# stspin32f0_rev_0_9.net
KiCad netlist of a schematic drawn in EAGLE
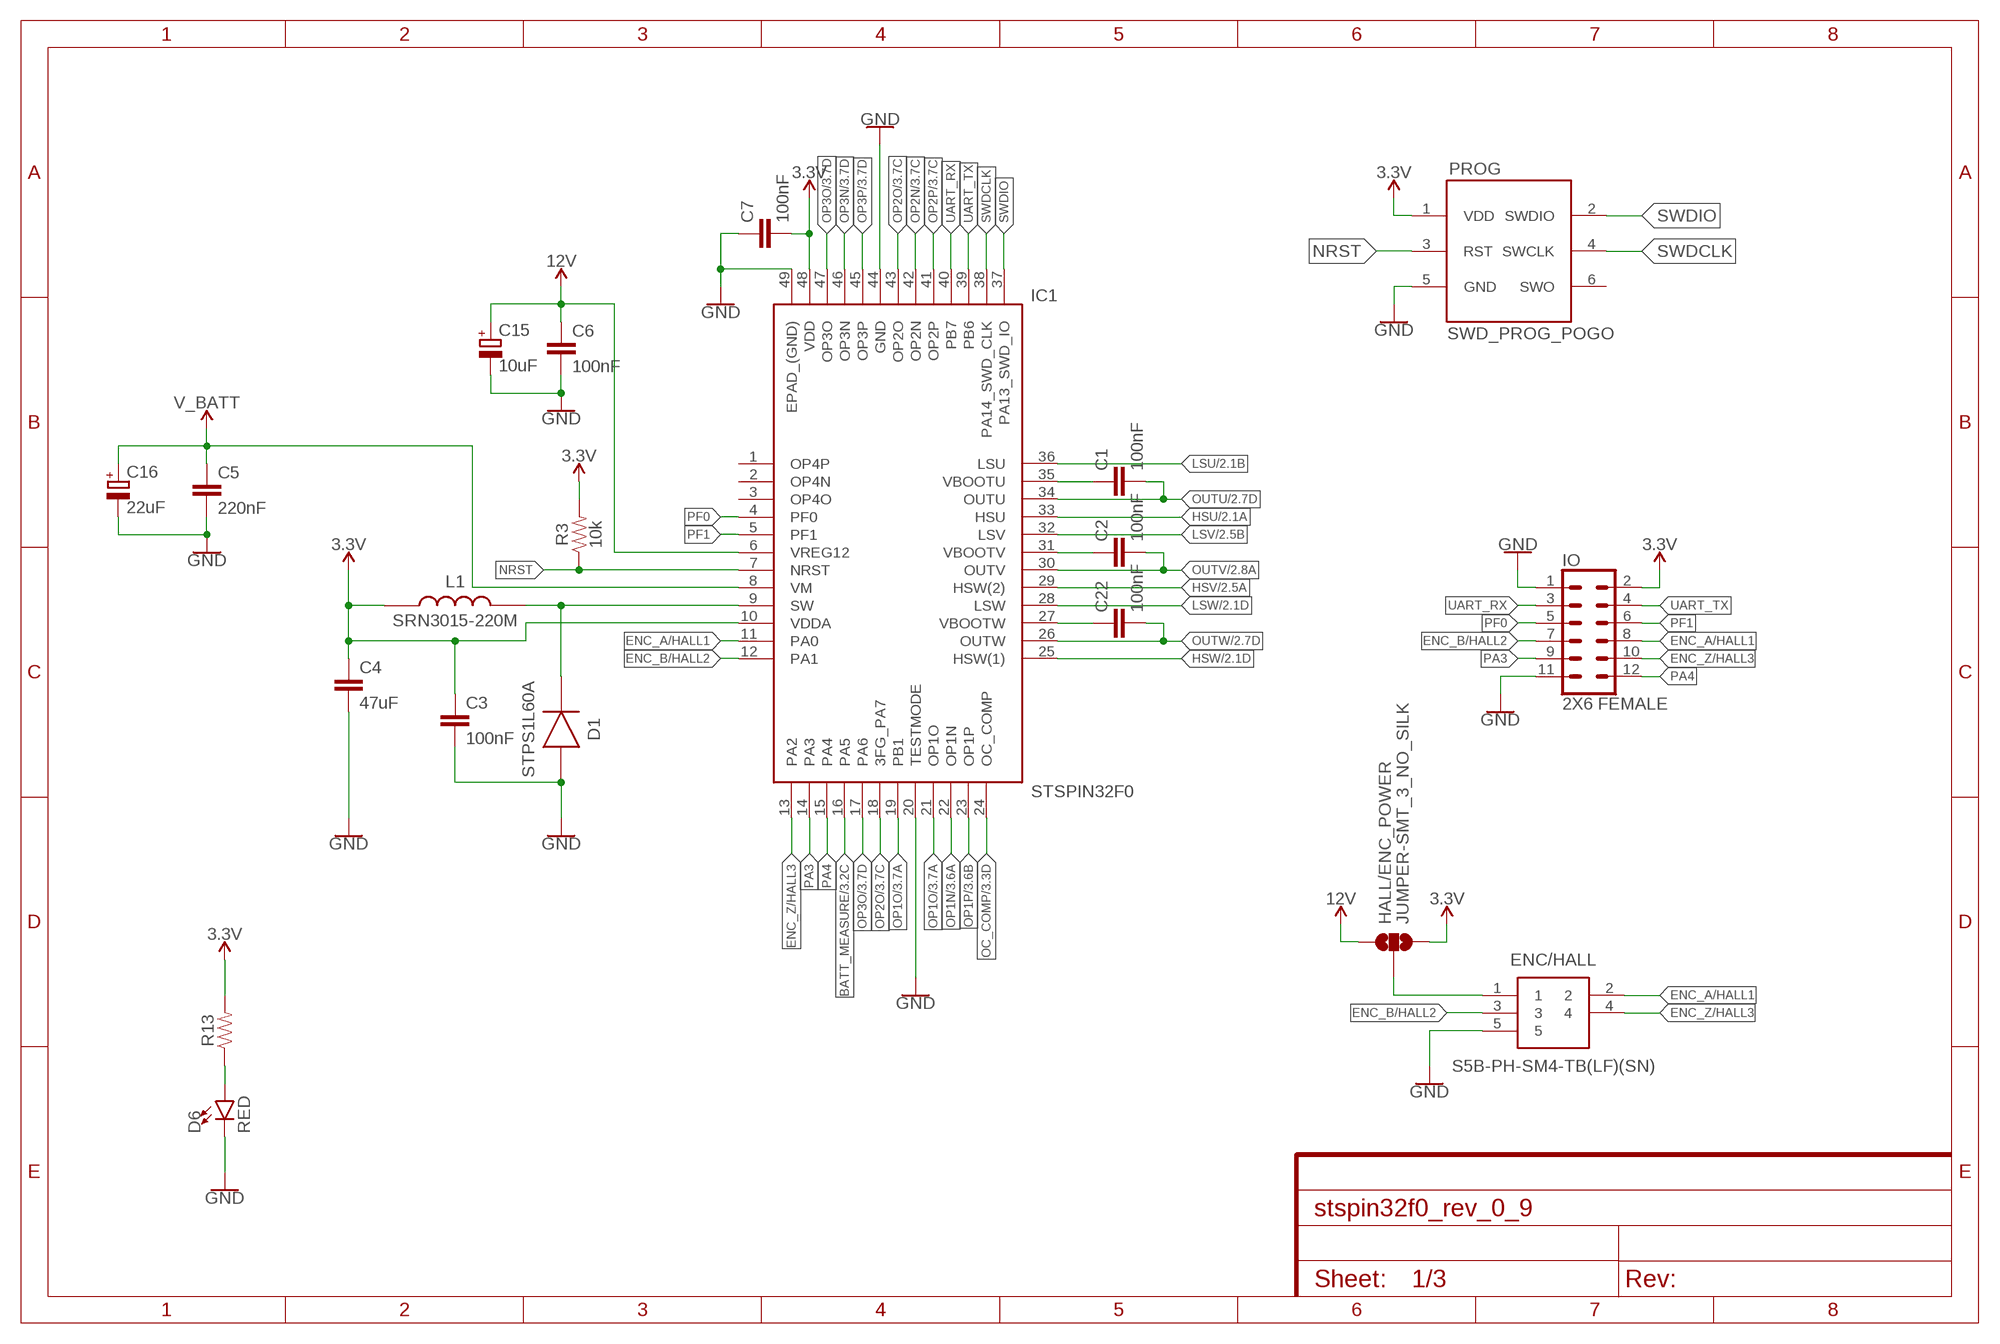
[diagram p0: schematic, sheet 1]
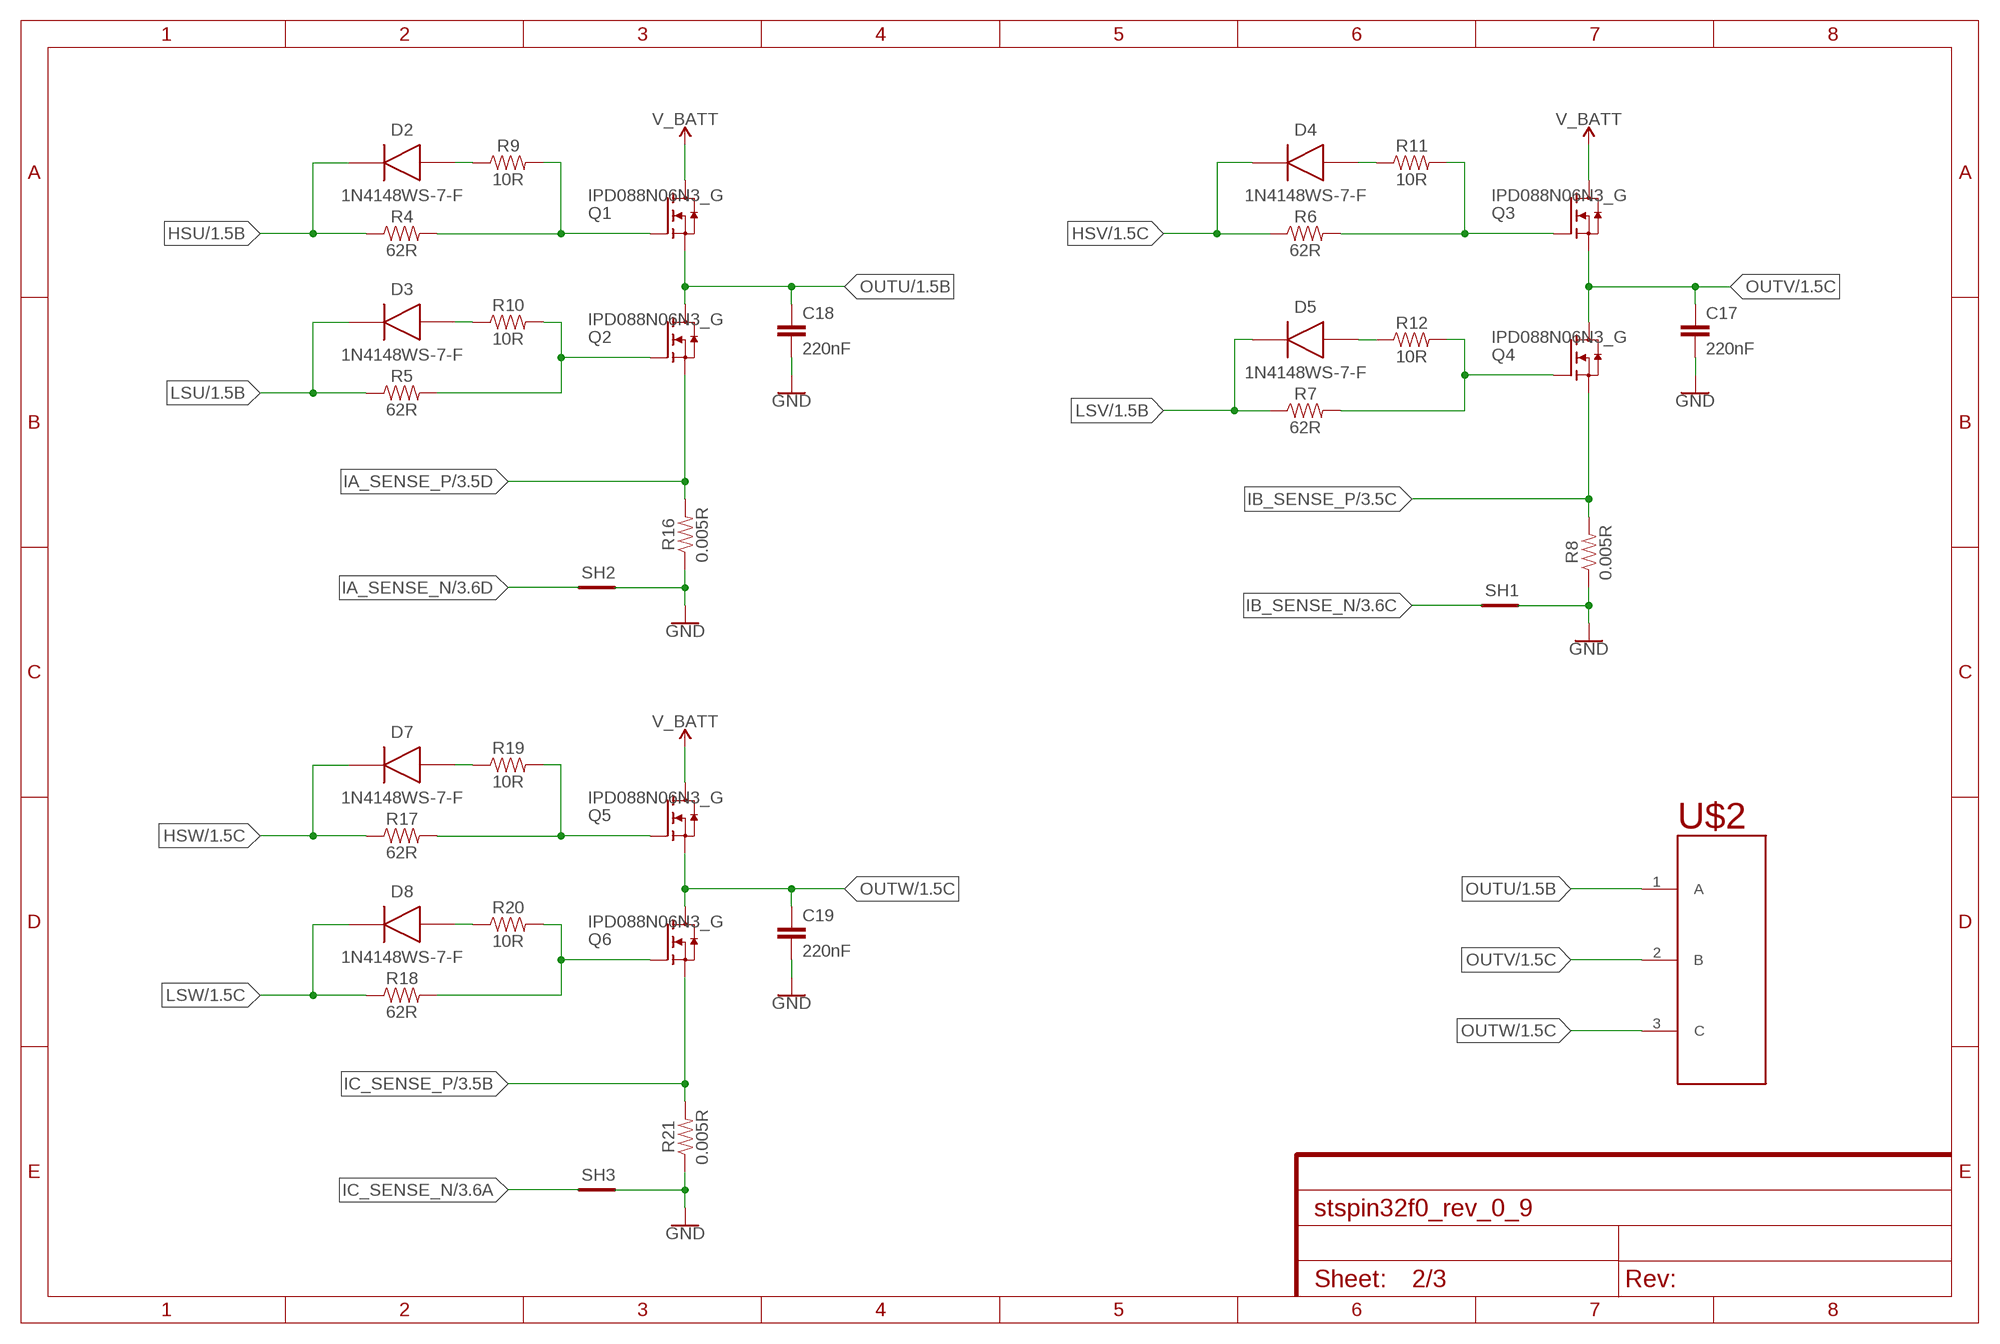
[diagram p1: schematic, sheet 2]
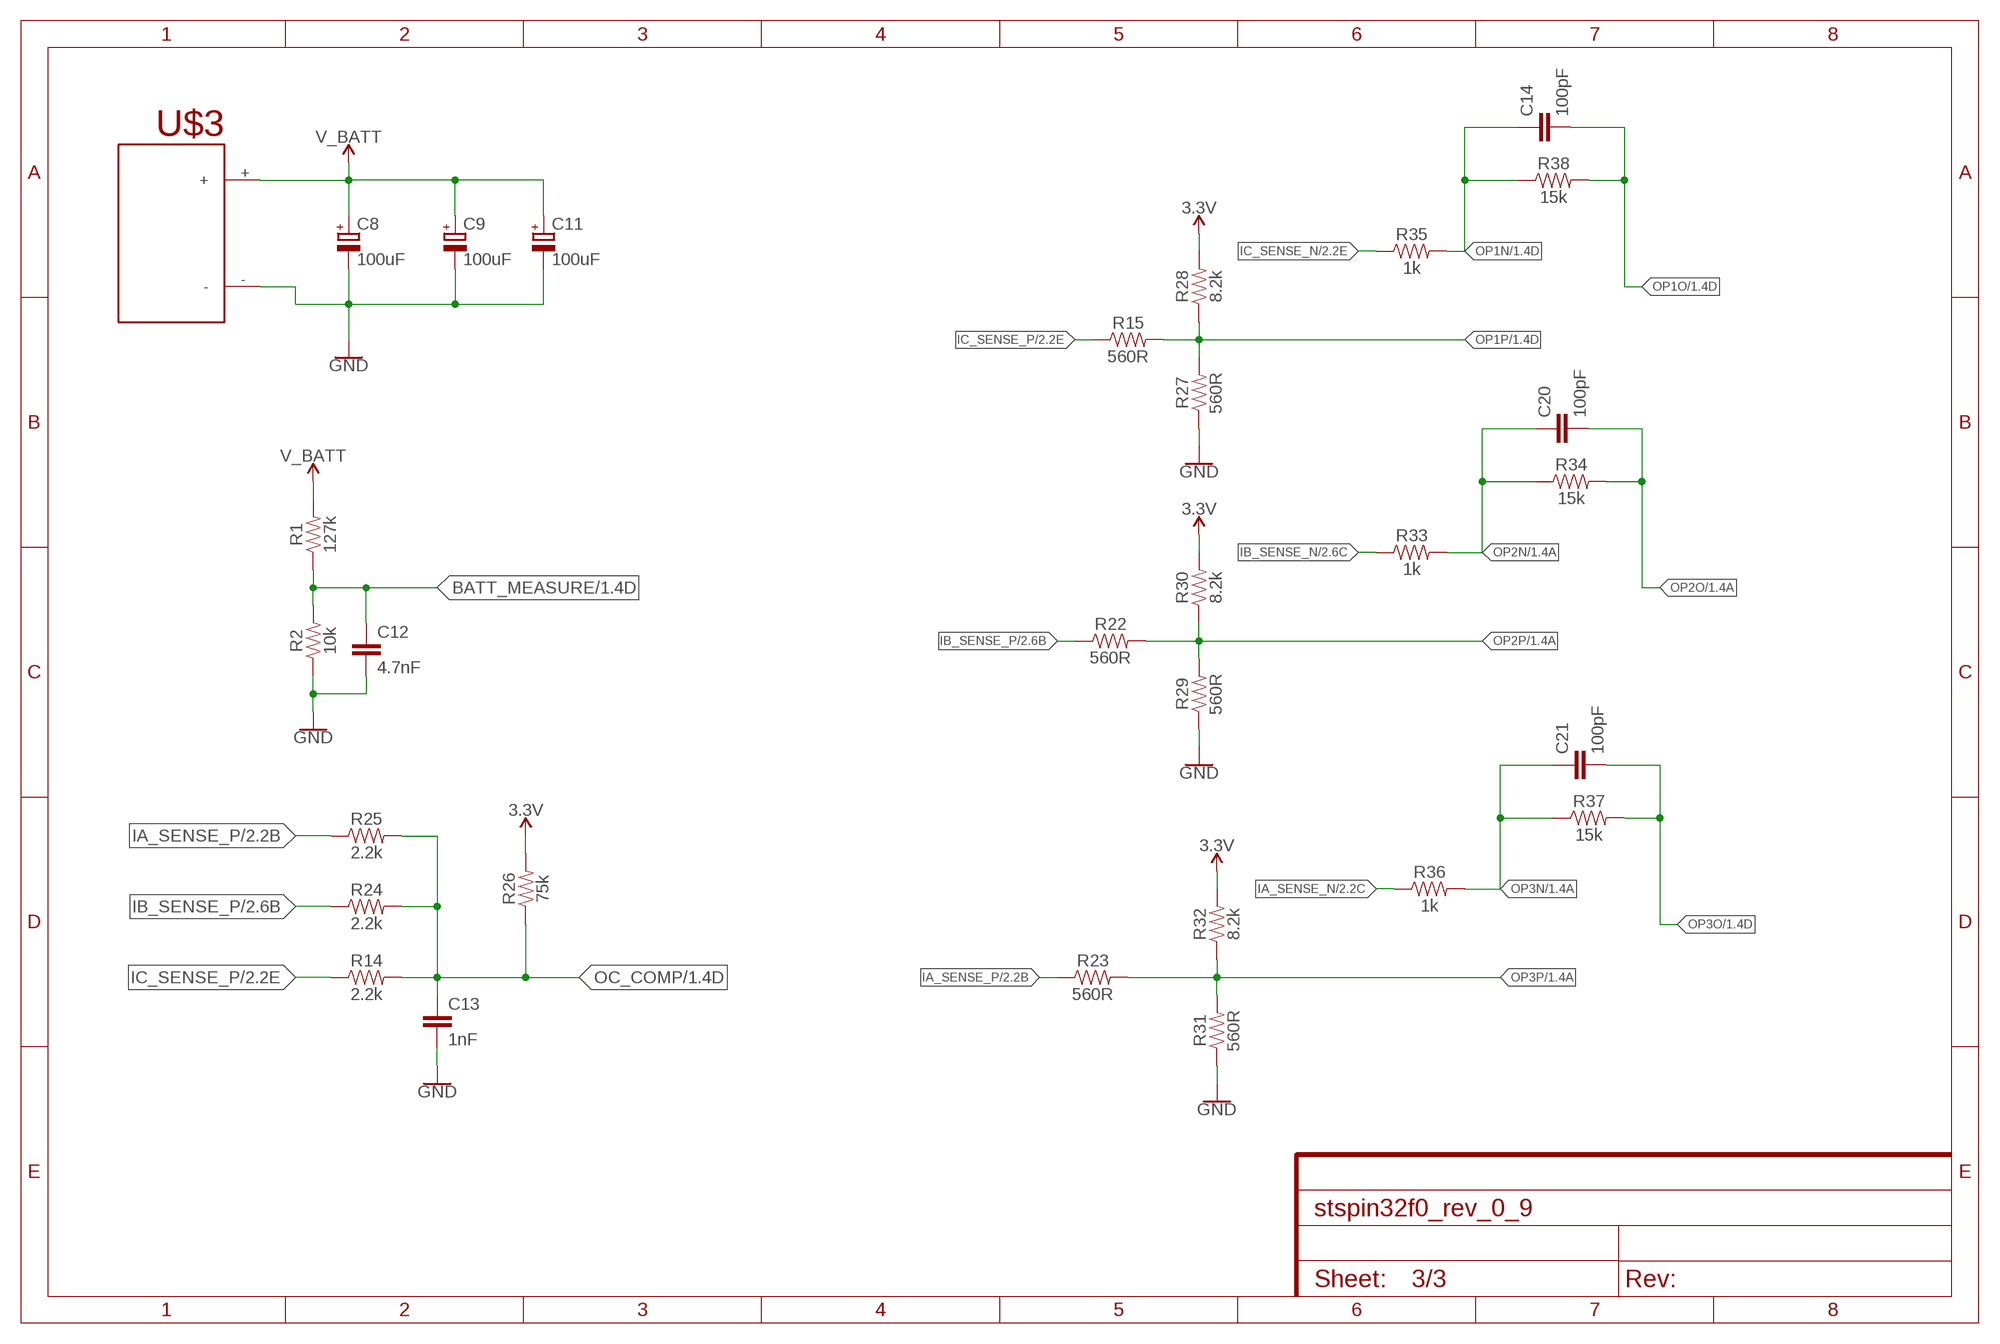
[diagram p2: schematic, sheet 3]

(export (version "E")
  (design (tool "Eeschema 10.0.6"))
  (components
    (comp (ref "C1")
      (value "100nF")
      (footprint "eagle-import:0603")
      (libsource (lib "eagle-import") (part "CAP-50V-10%-0603"))
    )
    (comp (ref "C2")
      (value "100nF")
      (footprint "eagle-import:0603")
      (libsource (lib "eagle-import") (part "CAP-50V-10%-0603"))
    )
    (comp (ref "C3")
      (value "100nF")
      (footprint "eagle-import:0603")
      (libsource (lib "eagle-import") (part "CAP-10V-20%-0603"))
    )
    (comp (ref "C4")
      (value "47uF")
      (footprint "eagle-import:0805")
      (libsource (lib "eagle-import") (part "CAP-10V-20%-0805"))
    )
    (comp (ref "C5")
      (value "220nF")
      (footprint "eagle-import:0805")
      (libsource (lib "eagle-import") (part "CAP-50V-10%-0805"))
    )
    (comp (ref "C6")
      (value "100nF")
      (footprint "eagle-import:0603")
      (libsource (lib "eagle-import") (part "CAP-25V-20%-0603"))
    )
    (comp (ref "C7")
      (value "100nF")
      (footprint "eagle-import:0603")
      (libsource (lib "eagle-import") (part "CAP-10V-20%-0603"))
    )
    (comp (ref "C15")
      (value "10uF")
      (footprint "eagle-import:UD-5X5,8_NICHICON")
      (libsource (lib "eagle-import") (part "CPOL-EUUD-5X5,8"))
    )
    (comp (ref "C16")
      (value "22uF")
      (footprint "eagle-import:UD-6,3X5,8_NICHICON")
      (libsource (lib "eagle-import") (part "CPOL-EUUD-6,3X8,8"))
    )
    (comp (ref "C22")
      (value "100nF")
      (footprint "eagle-import:0603")
      (libsource (lib "eagle-import") (part "CAP-50V-10%-0603"))
    )
    (comp (ref "D1")
      (value "STPS1L60A")
      (footprint "eagle-import:DIOM5126X265N")
      (fields (field (name "RS_PART_NUMBER") "250549"))
      (libsource (lib "eagle-import") (part "STPS1L60A"))
    )
    (comp (ref "D6")
      (value "RED")
      (footprint "eagle-import:LED-0603")
      (libsource (lib "eagle-import") (part "LED-RED0603"))
    )
    (comp (ref "ENC/HALL")
      (value "S5B-PH-SM4-TB(LF)(SN)")
      (footprint "eagle-import:S5B-PH-SM4-TB_1")
      (libsource (lib "eagle-import") (part "S5B-PH-SM4-TB(LF)(SN)"))
    )
    (comp (ref "HALL/ENC_POWER")
      (value "JUMPER-SMT_3_NO_SILK")
      (footprint "eagle-import:SMT-JUMPER_3_NO_SILK")
      (libsource (lib "eagle-import") (part "JUMPER-SMT_3_NO_SILK"))
    )
    (comp (ref "IC1")
      (value "STSPIN32F0")
      (footprint "eagle-import:QFN50P700X700X100-49N")
      (libsource (lib "eagle-import") (part "STSPIN32F0"))
    )
    (comp (ref "IO")
      (value "2X6 FEMALE")
      (footprint "eagle-import:2X6")
      (libsource (lib "eagle-import") (part "CONN_06X2PTH_FEMALE"))
    )
    (comp (ref "L1")
      (value "SRN3015-220M")
      (footprint "eagle-import:SRN3015")
      (fields (field (name "RS_PART_NUMBER") "7435087"))
      (libsource (lib "eagle-import") (part "SRN3015-220M"))
    )
    (comp (ref "PROG")
      (value "SWD_PROG_POGO")
      (footprint "eagle-import:1X06_1.27MM")
      (libsource (lib "eagle-import") (part "SWD_PROG_POGO"))
    )
    (comp (ref "R3")
      (value "10k")
      (footprint "eagle-import:0603")
      (libsource (lib "eagle-import") (part "RES-1/10W-5%-0603"))
    )
    (comp (ref "R13")
      (value "RES-1/10W-5%-0603")
      (footprint "eagle-import:0603")
      (libsource (lib "eagle-import") (part "RES-1/10W-5%-0603"))
    )
    (comp (ref "C17")
      (value "220nF")
      (footprint "eagle-import:0805")
      (libsource (lib "eagle-import") (part "CAP-50V-10%-0805"))
    )
    (comp (ref "C18")
      (value "220nF")
      (footprint "eagle-import:0805")
      (libsource (lib "eagle-import") (part "CAP-50V-10%-0805"))
    )
    (comp (ref "C19")
      (value "220nF")
      (footprint "eagle-import:0805")
      (libsource (lib "eagle-import") (part "CAP-50V-10%-0805"))
    )
    (comp (ref "D2")
      (value "1N4148WS-7-F")
      (footprint "eagle-import:SOD2513X120N")
      (fields (field (name "RS_PART_NUMBER") "9228070"))
      (libsource (lib "eagle-import") (part "1N4148WS-7-F"))
    )
    (comp (ref "D3")
      (value "1N4148WS-7-F")
      (footprint "eagle-import:SOD2513X120N")
      (fields (field (name "RS_PART_NUMBER") "9228070"))
      (libsource (lib "eagle-import") (part "1N4148WS-7-F"))
    )
    (comp (ref "D4")
      (value "1N4148WS-7-F")
      (footprint "eagle-import:SOD2513X120N")
      (fields (field (name "RS_PART_NUMBER") "9228070"))
      (libsource (lib "eagle-import") (part "1N4148WS-7-F"))
    )
    (comp (ref "D5")
      (value "1N4148WS-7-F")
      (footprint "eagle-import:SOD2513X120N")
      (fields (field (name "RS_PART_NUMBER") "9228070"))
      (libsource (lib "eagle-import") (part "1N4148WS-7-F"))
    )
    (comp (ref "D7")
      (value "1N4148WS-7-F")
      (footprint "eagle-import:SOD2513X120N")
      (fields (field (name "RS_PART_NUMBER") "9228070"))
      (libsource (lib "eagle-import") (part "1N4148WS-7-F"))
    )
    (comp (ref "D8")
      (value "1N4148WS-7-F")
      (footprint "eagle-import:SOD2513X120N")
      (fields (field (name "RS_PART_NUMBER") "9228070"))
      (libsource (lib "eagle-import") (part "1N4148WS-7-F"))
    )
    (comp (ref "Q1")
      (value "IPD088N06N3_G")
      (footprint "eagle-import:DPAK(TO-252-3)")
      (fields (field (name "MANUFACTURER_PART_NUMBER") "IPD088N06N3 G"))
      (libsource (lib "eagle-import") (part "IPD088N06N3_G"))
    )
    (comp (ref "Q2")
      (value "IPD088N06N3_G")
      (footprint "eagle-import:DPAK(TO-252-3)")
      (fields (field (name "MANUFACTURER_PART_NUMBER") "IPD088N06N3 G"))
      (libsource (lib "eagle-import") (part "IPD088N06N3_G"))
    )
    (comp (ref "Q3")
      (value "IPD088N06N3_G")
      (footprint "eagle-import:DPAK(TO-252-3)")
      (fields (field (name "MANUFACTURER_PART_NUMBER") "IPD088N06N3 G"))
      (libsource (lib "eagle-import") (part "IPD088N06N3_G"))
    )
    (comp (ref "Q4")
      (value "IPD088N06N3_G")
      (footprint "eagle-import:DPAK(TO-252-3)")
      (fields (field (name "MANUFACTURER_PART_NUMBER") "IPD088N06N3 G"))
      (libsource (lib "eagle-import") (part "IPD088N06N3_G"))
    )
    (comp (ref "Q5")
      (value "IPD088N06N3_G")
      (footprint "eagle-import:DPAK(TO-252-3)")
      (fields (field (name "MANUFACTURER_PART_NUMBER") "IPD088N06N3 G"))
      (libsource (lib "eagle-import") (part "IPD088N06N3_G"))
    )
    (comp (ref "Q6")
      (value "IPD088N06N3_G")
      (footprint "eagle-import:DPAK(TO-252-3)")
      (fields (field (name "MANUFACTURER_PART_NUMBER") "IPD088N06N3 G"))
      (libsource (lib "eagle-import") (part "IPD088N06N3_G"))
    )
    (comp (ref "R4")
      (value "62R")
      (footprint "eagle-import:0603")
      (libsource (lib "eagle-import") (part "RES-1/10W-5%-0603"))
    )
    (comp (ref "R5")
      (value "62R")
      (footprint "eagle-import:0603")
      (libsource (lib "eagle-import") (part "RES-1/10W-5%-0603"))
    )
    (comp (ref "R6")
      (value "62R")
      (footprint "eagle-import:0603")
      (libsource (lib "eagle-import") (part "RES-1/10W-5%-0603"))
    )
    (comp (ref "R7")
      (value "62R")
      (footprint "eagle-import:0603")
      (libsource (lib "eagle-import") (part "RES-1/10W-5%-0603"))
    )
    (comp (ref "R8")
      (value "0.005R")
      (footprint "eagle-import:R2512")
      (libsource (lib "eagle-import") (part "RES-3W-1%-2512"))
    )
    (comp (ref "R9")
      (value "10R")
      (footprint "eagle-import:0603")
      (libsource (lib "eagle-import") (part "RES-1/10W-5%-0603"))
    )
    (comp (ref "R10")
      (value "10R")
      (footprint "eagle-import:0603")
      (libsource (lib "eagle-import") (part "RES-1/10W-5%-0603"))
    )
    (comp (ref "R11")
      (value "10R")
      (footprint "eagle-import:0603")
      (libsource (lib "eagle-import") (part "RES-1/10W-5%-0603"))
    )
    (comp (ref "R12")
      (value "10R")
      (footprint "eagle-import:0603")
      (libsource (lib "eagle-import") (part "RES-1/10W-5%-0603"))
    )
    (comp (ref "R16")
      (value "0.005R")
      (footprint "eagle-import:R2512")
      (libsource (lib "eagle-import") (part "RES-3W-1%-2512"))
    )
    (comp (ref "R17")
      (value "62R")
      (footprint "eagle-import:0603")
      (libsource (lib "eagle-import") (part "RES-1/10W-5%-0603"))
    )
    (comp (ref "R18")
      (value "62R")
      (footprint "eagle-import:0603")
      (libsource (lib "eagle-import") (part "RES-1/10W-5%-0603"))
    )
    (comp (ref "R19")
      (value "10R")
      (footprint "eagle-import:0603")
      (libsource (lib "eagle-import") (part "RES-1/10W-5%-0603"))
    )
    (comp (ref "R20")
      (value "10R")
      (footprint "eagle-import:0603")
      (libsource (lib "eagle-import") (part "RES-1/10W-5%-0603"))
    )
    (comp (ref "R21")
      (value "0.005R")
      (footprint "eagle-import:R2512")
      (libsource (lib "eagle-import") (part "RES-3W-1%-2512"))
    )
    (comp (ref "SH1")
      (value "SHORTT5")
      (footprint "eagle-import:SHORT_TOP-50")
      (libsource (lib "eagle-import") (part "SHORTT5"))
    )
    (comp (ref "SH2")
      (value "SHORTT5")
      (footprint "eagle-import:SHORT_TOP-50")
      (libsource (lib "eagle-import") (part "SHORTT5"))
    )
    (comp (ref "SH3")
      (value "SHORTT5")
      (footprint "eagle-import:SHORT_TOP-50")
      (libsource (lib "eagle-import") (part "SHORTT5"))
    )
    (comp (ref "U$2")
      (value "MR30")
      (footprint "eagle-import:MR30PW")
      (libsource (lib "eagle-import") (part "MR30"))
    )
    (comp (ref "C8")
      (value "100uF")
      (footprint "eagle-import:UD-6,3X7,7_NICHICON")
      (libsource (lib "eagle-import") (part "CPOL-EUUD-6,3X7,7"))
    )
    (comp (ref "C9")
      (value "100uF")
      (footprint "eagle-import:UD-6,3X7,7_NICHICON")
      (libsource (lib "eagle-import") (part "CPOL-EUUD-6,3X7,7"))
    )
    (comp (ref "C11")
      (value "100uF")
      (footprint "eagle-import:UD-6,3X7,7_NICHICON")
      (libsource (lib "eagle-import") (part "CPOL-EUUD-6,3X7,7"))
    )
    (comp (ref "C12")
      (value "4.7nF")
      (footprint "eagle-import:0603")
      (libsource (lib "eagle-import") (part "CAP-25V-20%-0603"))
    )
    (comp (ref "C13")
      (value "1nF")
      (footprint "eagle-import:0603")
      (libsource (lib "eagle-import") (part "CAP-25V-20%-0603"))
    )
    (comp (ref "C14")
      (value "100pF")
      (footprint "eagle-import:0603")
      (libsource (lib "eagle-import") (part "CAP-25V-20%-0603"))
    )
    (comp (ref "C20")
      (value "100pF")
      (footprint "eagle-import:0603")
      (libsource (lib "eagle-import") (part "CAP-25V-20%-0603"))
    )
    (comp (ref "C21")
      (value "100pF")
      (footprint "eagle-import:0603")
      (libsource (lib "eagle-import") (part "CAP-25V-20%-0603"))
    )
    (comp (ref "R1")
      (value "127k")
      (footprint "eagle-import:0603")
      (libsource (lib "eagle-import") (part "RES-1/10W-1%-0603"))
    )
    (comp (ref "R2")
      (value "10k")
      (footprint "eagle-import:0603")
      (libsource (lib "eagle-import") (part "RES-1/10W-1%-0603"))
    )
    (comp (ref "R14")
      (value "2.2k")
      (footprint "eagle-import:0603")
      (libsource (lib "eagle-import") (part "RES-1/10W-5%-0603"))
    )
    (comp (ref "R15")
      (value "560R")
      (footprint "eagle-import:0603")
      (libsource (lib "eagle-import") (part "RES-1/10W-5%-0603"))
    )
    (comp (ref "R22")
      (value "560R")
      (footprint "eagle-import:0603")
      (libsource (lib "eagle-import") (part "RES-1/10W-5%-0603"))
    )
    (comp (ref "R23")
      (value "560R")
      (footprint "eagle-import:0603")
      (libsource (lib "eagle-import") (part "RES-1/10W-5%-0603"))
    )
    (comp (ref "R24")
      (value "2.2k")
      (footprint "eagle-import:0603")
      (libsource (lib "eagle-import") (part "RES-1/10W-5%-0603"))
    )
    (comp (ref "R25")
      (value "2.2k")
      (footprint "eagle-import:0603")
      (libsource (lib "eagle-import") (part "RES-1/10W-5%-0603"))
    )
    (comp (ref "R26")
      (value "75k")
      (footprint "eagle-import:0603")
      (libsource (lib "eagle-import") (part "RES-1/10W-1%-0603"))
    )
    (comp (ref "R27")
      (value "560R")
      (footprint "eagle-import:0603")
      (libsource (lib "eagle-import") (part "RES-1/10W-5%-0603"))
    )
    (comp (ref "R28")
      (value "8.2k")
      (footprint "eagle-import:0603")
      (libsource (lib "eagle-import") (part "RES-1/10W-5%-0603"))
    )
    (comp (ref "R29")
      (value "560R")
      (footprint "eagle-import:0603")
      (libsource (lib "eagle-import") (part "RES-1/10W-5%-0603"))
    )
    (comp (ref "R30")
      (value "8.2k")
      (footprint "eagle-import:0603")
      (libsource (lib "eagle-import") (part "RES-1/10W-5%-0603"))
    )
    (comp (ref "R31")
      (value "560R")
      (footprint "eagle-import:0603")
      (libsource (lib "eagle-import") (part "RES-1/10W-5%-0603"))
    )
    (comp (ref "R32")
      (value "8.2k")
      (footprint "eagle-import:0603")
      (libsource (lib "eagle-import") (part "RES-1/10W-5%-0603"))
    )
    (comp (ref "R33")
      (value "1k")
      (footprint "eagle-import:0603")
      (libsource (lib "eagle-import") (part "RES-1/10W-5%-0603"))
    )
    (comp (ref "R34")
      (value "15k")
      (footprint "eagle-import:0603")
      (libsource (lib "eagle-import") (part "RES-1/10W-5%-0603"))
    )
    (comp (ref "R35")
      (value "1k")
      (footprint "eagle-import:0603")
      (libsource (lib "eagle-import") (part "RES-1/10W-5%-0603"))
    )
    (comp (ref "R36")
      (value "1k")
      (footprint "eagle-import:0603")
      (libsource (lib "eagle-import") (part "RES-1/10W-5%-0603"))
    )
    (comp (ref "R37")
      (value "15k")
      (footprint "eagle-import:0603")
      (libsource (lib "eagle-import") (part "RES-1/10W-5%-0603"))
    )
    (comp (ref "R38")
      (value "15k")
      (footprint "eagle-import:0603")
      (libsource (lib "eagle-import") (part "RES-1/10W-5%-0603"))
    )
    (comp (ref "U$3")
      (value "XT30")
      (footprint "eagle-import:XT30PW")
      (libsource (lib "eagle-import") (part "XT30"))
    )
  )
  (nets
    (net (code "1") (name "3.3V") (class "Default")
      (node (ref "C3") (pin "1") (pinfunction "1_1") (pintype "passive"))
      (node (ref "C4") (pin "1") (pinfunction "1_1") (pintype "passive"))
      (node (ref "C7") (pin "2") (pinfunction "2_2") (pintype "passive"))
      (node (ref "HALL/ENC_POWER") (pin "3") (pinfunction "3_3") (pintype "passive"))
      (node (ref "IC1") (pin "10") (pinfunction "VDDA_10") (pintype "input"))
      (node (ref "IC1") (pin "48") (pinfunction "VDD_48") (pintype "input"))
      (node (ref "IO") (pin "2") (pinfunction "2_2") (pintype "passive"))
      (node (ref "L1") (pin "1") (pinfunction "1_1") (pintype "bidirectional"))
      (node (ref "PROG") (pin "1") (pinfunction "VDD_1") (pintype "bidirectional"))
      (node (ref "R13") (pin "2") (pinfunction "2_2") (pintype "passive"))
      (node (ref "R26") (pin "2") (pinfunction "2_2") (pintype "passive"))
      (node (ref "R28") (pin "2") (pinfunction "2_2") (pintype "passive"))
      (node (ref "R3") (pin "2") (pinfunction "2_2") (pintype "passive"))
      (node (ref "R30") (pin "2") (pinfunction "2_2") (pintype "passive"))
      (node (ref "R32") (pin "2") (pinfunction "2_2") (pintype "passive"))
    )
    (net (code "2") (name "12V") (class "Default")
      (node (ref "C15") (pin "+") (pinfunction "+_+") (pintype "passive"))
      (node (ref "C6") (pin "1") (pinfunction "1_1") (pintype "passive"))
      (node (ref "HALL/ENC_POWER") (pin "1") (pinfunction "1_1") (pintype "passive"))
      (node (ref "IC1") (pin "6") (pinfunction "VREG12_6") (pintype "input"))
    )
    (net (code "3") (name "BATT_MEASURE") (class "Default")
      (node (ref "C12") (pin "1") (pinfunction "1_1") (pintype "passive"))
      (node (ref "IC1") (pin "16") (pinfunction "PA5_16") (pintype "input"))
      (node (ref "R1") (pin "1") (pinfunction "1_1") (pintype "passive"))
      (node (ref "R2") (pin "2") (pinfunction "2_2") (pintype "passive"))
    )
    (net (code "4") (name "ENC_A{slash}HALL1") (class "Default")
      (node (ref "ENC/HALL") (pin "2") (pinfunction "2_2") (pintype "input"))
      (node (ref "IC1") (pin "11") (pinfunction "PA0_11") (pintype "input"))
      (node (ref "IO") (pin "8") (pinfunction "8_8") (pintype "passive"))
    )
    (net (code "5") (name "ENC_B{slash}HALL2") (class "Default")
      (node (ref "ENC/HALL") (pin "3") (pinfunction "3_3") (pintype "input"))
      (node (ref "IC1") (pin "12") (pinfunction "PA1_12") (pintype "input"))
      (node (ref "IO") (pin "7") (pinfunction "7_7") (pintype "passive"))
    )
    (net (code "6") (name "ENC_Z{slash}HALL3") (class "Default")
      (node (ref "ENC/HALL") (pin "4") (pinfunction "4_4") (pintype "input"))
      (node (ref "IC1") (pin "13") (pinfunction "PA2_13") (pintype "input"))
      (node (ref "IO") (pin "10") (pinfunction "10_10") (pintype "passive"))
    )
    (net (code "7") (name "GND") (class "Default")
      (node (ref "C11") (pin "-") (pinfunction "-_-") (pintype "passive"))
      (node (ref "C12") (pin "2") (pinfunction "2_2") (pintype "passive"))
      (node (ref "C13") (pin "2") (pinfunction "2_2") (pintype "passive"))
      (node (ref "C15") (pin "-") (pinfunction "-_-") (pintype "passive"))
      (node (ref "C16") (pin "-") (pinfunction "-_-") (pintype "passive"))
      (node (ref "C17") (pin "2") (pinfunction "2_2") (pintype "passive"))
      (node (ref "C18") (pin "2") (pinfunction "2_2") (pintype "passive"))
      (node (ref "C19") (pin "2") (pinfunction "2_2") (pintype "passive"))
      (node (ref "C3") (pin "2") (pinfunction "2_2") (pintype "passive"))
      (node (ref "C4") (pin "2") (pinfunction "2_2") (pintype "passive"))
      (node (ref "C5") (pin "2") (pinfunction "2_2") (pintype "passive"))
      (node (ref "C6") (pin "2") (pinfunction "2_2") (pintype "passive"))
      (node (ref "C7") (pin "1") (pinfunction "1_1") (pintype "passive"))
      (node (ref "C8") (pin "-") (pinfunction "-_-") (pintype "passive"))
      (node (ref "C9") (pin "-") (pinfunction "-_-") (pintype "passive"))
      (node (ref "D1") (pin "2") (pinfunction "A_2") (pintype "bidirectional"))
      (node (ref "D6") (pin "C") (pinfunction "C_C") (pintype "passive"))
      (node (ref "ENC/HALL") (pin "5") (pinfunction "5_5") (pintype "input"))
      (node (ref "IC1") (pin "20") (pinfunction "TESTMODE_20") (pintype "input"))
      (node (ref "IC1") (pin "44") (pinfunction "GND_44") (pintype "input"))
      (node (ref "IC1") (pin "49") (pinfunction "EPAD_(GND)_49") (pintype "input"))
      (node (ref "IO") (pin "1") (pinfunction "1_1") (pintype "passive"))
      (node (ref "IO") (pin "11") (pinfunction "11_11") (pintype "passive"))
      (node (ref "PROG") (pin "5") (pinfunction "GND_5") (pintype "bidirectional"))
      (node (ref "R16") (pin "1") (pinfunction "1_1") (pintype "passive"))
      (node (ref "R2") (pin "1") (pinfunction "1_1") (pintype "passive"))
      (node (ref "R21") (pin "1") (pinfunction "1_1") (pintype "passive"))
      (node (ref "R27") (pin "1") (pinfunction "1_1") (pintype "passive"))
      (node (ref "R29") (pin "1") (pinfunction "1_1") (pintype "passive"))
      (node (ref "R31") (pin "1") (pinfunction "1_1") (pintype "passive"))
      (node (ref "R8") (pin "1") (pinfunction "1_1") (pintype "passive"))
      (node (ref "SH1") (pin "2") (pinfunction "P$2_2") (pintype "bidirectional"))
      (node (ref "SH2") (pin "2") (pinfunction "P$2_2") (pintype "bidirectional"))
      (node (ref "SH3") (pin "2") (pinfunction "P$2_2") (pintype "bidirectional"))
      (node (ref "U$3") (pin "-") (pinfunction "-_-") (pintype "bidirectional"))
    )
    (net (code "8") (name "HSU") (class "Default")
      (node (ref "D2") (pin "1") (pinfunction "K_1") (pintype "bidirectional"))
      (node (ref "IC1") (pin "33") (pinfunction "HSU_33") (pintype "input"))
      (node (ref "R4") (pin "1") (pinfunction "1_1") (pintype "passive"))
    )
    (net (code "9") (name "HSV") (class "Default")
      (node (ref "D4") (pin "1") (pinfunction "K_1") (pintype "bidirectional"))
      (node (ref "IC1") (pin "29") (pinfunction "HSW(2)_29") (pintype "input"))
      (node (ref "R6") (pin "1") (pinfunction "1_1") (pintype "passive"))
    )
    (net (code "10") (name "HSW") (class "Default")
      (node (ref "D7") (pin "1") (pinfunction "K_1") (pintype "bidirectional"))
      (node (ref "IC1") (pin "25") (pinfunction "HSW(1)_25") (pintype "input"))
      (node (ref "R17") (pin "1") (pinfunction "1_1") (pintype "passive"))
    )
    (net (code "11") (name "IA_SENSE_N") (class "Default")
      (node (ref "R36") (pin "1") (pinfunction "1_1") (pintype "passive"))
      (node (ref "SH2") (pin "1") (pinfunction "P$1_1") (pintype "bidirectional"))
    )
    (net (code "12") (name "IA_SENSE_P") (class "Default")
      (node (ref "Q2") (pin "3") (pinfunction "S_3") (pintype "passive"))
      (node (ref "R16") (pin "2") (pinfunction "2_2") (pintype "passive"))
      (node (ref "R23") (pin "1") (pinfunction "1_1") (pintype "passive"))
      (node (ref "R25") (pin "1") (pinfunction "1_1") (pintype "passive"))
    )
    (net (code "13") (name "IB_SENSE_N") (class "Default")
      (node (ref "R33") (pin "1") (pinfunction "1_1") (pintype "passive"))
      (node (ref "SH1") (pin "1") (pinfunction "P$1_1") (pintype "bidirectional"))
    )
    (net (code "14") (name "IB_SENSE_P") (class "Default")
      (node (ref "Q4") (pin "3") (pinfunction "S_3") (pintype "passive"))
      (node (ref "R22") (pin "1") (pinfunction "1_1") (pintype "passive"))
      (node (ref "R24") (pin "1") (pinfunction "1_1") (pintype "passive"))
      (node (ref "R8") (pin "2") (pinfunction "2_2") (pintype "passive"))
    )
    (net (code "15") (name "IC_SENSE_N") (class "Default")
      (node (ref "R35") (pin "1") (pinfunction "1_1") (pintype "passive"))
      (node (ref "SH3") (pin "1") (pinfunction "P$1_1") (pintype "bidirectional"))
    )
    (net (code "16") (name "IC_SENSE_P") (class "Default")
      (node (ref "Q6") (pin "3") (pinfunction "S_3") (pintype "passive"))
      (node (ref "R14") (pin "1") (pinfunction "1_1") (pintype "passive"))
      (node (ref "R15") (pin "1") (pinfunction "1_1") (pintype "passive"))
      (node (ref "R21") (pin "2") (pinfunction "2_2") (pintype "passive"))
    )
    (net (code "17") (name "LSU") (class "Default")
      (node (ref "D3") (pin "1") (pinfunction "K_1") (pintype "bidirectional"))
      (node (ref "IC1") (pin "36") (pinfunction "LSU_36") (pintype "input"))
      (node (ref "R5") (pin "1") (pinfunction "1_1") (pintype "passive"))
    )
    (net (code "18") (name "LSV") (class "Default")
      (node (ref "D5") (pin "1") (pinfunction "K_1") (pintype "bidirectional"))
      (node (ref "IC1") (pin "32") (pinfunction "LSV_32") (pintype "input"))
      (node (ref "R7") (pin "1") (pinfunction "1_1") (pintype "passive"))
    )
    (net (code "19") (name "LSW") (class "Default")
      (node (ref "D8") (pin "1") (pinfunction "K_1") (pintype "bidirectional"))
      (node (ref "IC1") (pin "28") (pinfunction "LSW_28") (pintype "input"))
      (node (ref "R18") (pin "1") (pinfunction "1_1") (pintype "passive"))
    )
    (net (code "20") (name "NRST") (class "Default")
      (node (ref "IC1") (pin "7") (pinfunction "NRST_7") (pintype "input"))
      (node (ref "PROG") (pin "3") (pinfunction "RST_3") (pintype "bidirectional"))
      (node (ref "R3") (pin "1") (pinfunction "1_1") (pintype "passive"))
    )
    (net (code "21") (name "Net-(D1-K)") (class "Default")
      (node (ref "D1") (pin "1") (pinfunction "K_1") (pintype "bidirectional"))
      (node (ref "IC1") (pin "9") (pinfunction "SW_9") (pintype "input"))
      (node (ref "L1") (pin "2") (pinfunction "2_2") (pintype "bidirectional"))
    )
    (net (code "22") (name "Net-(D2-A)") (class "Default")
      (node (ref "D2") (pin "2") (pinfunction "A_2") (pintype "bidirectional"))
      (node (ref "R9") (pin "1") (pinfunction "1_1") (pintype "passive"))
    )
    (net (code "23") (name "Net-(D3-A)") (class "Default")
      (node (ref "D3") (pin "2") (pinfunction "A_2") (pintype "bidirectional"))
      (node (ref "R10") (pin "1") (pinfunction "1_1") (pintype "passive"))
    )
    (net (code "24") (name "Net-(D4-A)") (class "Default")
      (node (ref "D4") (pin "2") (pinfunction "A_2") (pintype "bidirectional"))
      (node (ref "R11") (pin "1") (pinfunction "1_1") (pintype "passive"))
    )
    (net (code "25") (name "Net-(D5-A)") (class "Default")
      (node (ref "D5") (pin "2") (pinfunction "A_2") (pintype "bidirectional"))
      (node (ref "R12") (pin "1") (pinfunction "1_1") (pintype "passive"))
    )
    (net (code "26") (name "Net-(D6-PadA)") (class "Default")
      (node (ref "D6") (pin "A") (pinfunction "A_A") (pintype "passive"))
      (node (ref "R13") (pin "1") (pinfunction "1_1") (pintype "passive"))
    )
    (net (code "27") (name "Net-(D7-A)") (class "Default")
      (node (ref "D7") (pin "2") (pinfunction "A_2") (pintype "bidirectional"))
      (node (ref "R19") (pin "1") (pinfunction "1_1") (pintype "passive"))
    )
    (net (code "28") (name "Net-(D8-A)") (class "Default")
      (node (ref "D8") (pin "2") (pinfunction "A_2") (pintype "bidirectional"))
      (node (ref "R20") (pin "1") (pinfunction "1_1") (pintype "passive"))
    )
    (net (code "29") (name "Net-(ENC/HALL-Pad1)") (class "Default")
      (node (ref "ENC/HALL") (pin "1") (pinfunction "1_1") (pintype "input"))
      (node (ref "HALL/ENC_POWER") (pin "2") (pinfunction "2_2") (pintype "passive"))
    )
    (net (code "30") (name "Net-(IC1-VBOOTU)") (class "Default")
      (node (ref "C1") (pin "1") (pinfunction "1_1") (pintype "passive"))
      (node (ref "IC1") (pin "35") (pinfunction "VBOOTU_35") (pintype "input"))
    )
    (net (code "31") (name "Net-(IC1-VBOOTV)") (class "Default")
      (node (ref "C2") (pin "1") (pinfunction "1_1") (pintype "passive"))
      (node (ref "IC1") (pin "31") (pinfunction "VBOOTV_31") (pintype "input"))
    )
    (net (code "32") (name "Net-(IC1-VBOOTW)") (class "Default")
      (node (ref "C22") (pin "1") (pinfunction "1_1") (pintype "passive"))
      (node (ref "IC1") (pin "27") (pinfunction "VBOOTW_27") (pintype "input"))
    )
    (net (code "33") (name "Net-(Q1-G)") (class "Default")
      (node (ref "Q1") (pin "1") (pinfunction "G_1") (pintype "passive"))
      (node (ref "R4") (pin "2") (pinfunction "2_2") (pintype "passive"))
      (node (ref "R9") (pin "2") (pinfunction "2_2") (pintype "passive"))
    )
    (net (code "34") (name "Net-(Q2-G)") (class "Default")
      (node (ref "Q2") (pin "1") (pinfunction "G_1") (pintype "passive"))
      (node (ref "R10") (pin "2") (pinfunction "2_2") (pintype "passive"))
      (node (ref "R5") (pin "2") (pinfunction "2_2") (pintype "passive"))
    )
    (net (code "35") (name "Net-(Q3-G)") (class "Default")
      (node (ref "Q3") (pin "1") (pinfunction "G_1") (pintype "passive"))
      (node (ref "R11") (pin "2") (pinfunction "2_2") (pintype "passive"))
      (node (ref "R6") (pin "2") (pinfunction "2_2") (pintype "passive"))
    )
    (net (code "36") (name "Net-(Q4-G)") (class "Default")
      (node (ref "Q4") (pin "1") (pinfunction "G_1") (pintype "passive"))
      (node (ref "R12") (pin "2") (pinfunction "2_2") (pintype "passive"))
      (node (ref "R7") (pin "2") (pinfunction "2_2") (pintype "passive"))
    )
    (net (code "37") (name "Net-(Q5-G)") (class "Default")
      (node (ref "Q5") (pin "1") (pinfunction "G_1") (pintype "passive"))
      (node (ref "R17") (pin "2") (pinfunction "2_2") (pintype "passive"))
      (node (ref "R19") (pin "2") (pinfunction "2_2") (pintype "passive"))
    )
    (net (code "38") (name "Net-(Q6-G)") (class "Default")
      (node (ref "Q6") (pin "1") (pinfunction "G_1") (pintype "passive"))
      (node (ref "R18") (pin "2") (pinfunction "2_2") (pintype "passive"))
      (node (ref "R20") (pin "2") (pinfunction "2_2") (pintype "passive"))
    )
    (net (code "39") (name "OC_COMP") (class "Default")
      (node (ref "C13") (pin "1") (pinfunction "1_1") (pintype "passive"))
      (node (ref "IC1") (pin "24") (pinfunction "OC_COMP_24") (pintype "input"))
      (node (ref "R14") (pin "2") (pinfunction "2_2") (pintype "passive"))
      (node (ref "R24") (pin "2") (pinfunction "2_2") (pintype "passive"))
      (node (ref "R25") (pin "2") (pinfunction "2_2") (pintype "passive"))
      (node (ref "R26") (pin "1") (pinfunction "1_1") (pintype "passive"))
    )
    (net (code "40") (name "OP1N") (class "Default")
      (node (ref "C14") (pin "1") (pinfunction "1_1") (pintype "passive"))
      (node (ref "IC1") (pin "22") (pinfunction "OP1N_22") (pintype "input"))
      (node (ref "R35") (pin "2") (pinfunction "2_2") (pintype "passive"))
      (node (ref "R38") (pin "1") (pinfunction "1_1") (pintype "passive"))
    )
    (net (code "41") (name "OP1O") (class "Default")
      (node (ref "C14") (pin "2") (pinfunction "2_2") (pintype "passive"))
      (node (ref "IC1") (pin "19") (pinfunction "PB1_19") (pintype "input"))
      (node (ref "IC1") (pin "21") (pinfunction "OP1O_21") (pintype "input"))
      (node (ref "R38") (pin "2") (pinfunction "2_2") (pintype "passive"))
    )
    (net (code "42") (name "OP1P") (class "Default")
      (node (ref "IC1") (pin "23") (pinfunction "OP1P_23") (pintype "input"))
      (node (ref "R15") (pin "2") (pinfunction "2_2") (pintype "passive"))
      (node (ref "R27") (pin "2") (pinfunction "2_2") (pintype "passive"))
      (node (ref "R28") (pin "1") (pinfunction "1_1") (pintype "passive"))
    )
    (net (code "43") (name "OP2N") (class "Default")
      (node (ref "C20") (pin "1") (pinfunction "1_1") (pintype "passive"))
      (node (ref "IC1") (pin "42") (pinfunction "OP2N_42") (pintype "input"))
      (node (ref "R33") (pin "2") (pinfunction "2_2") (pintype "passive"))
      (node (ref "R34") (pin "1") (pinfunction "1_1") (pintype "passive"))
    )
    (net (code "44") (name "OP2O") (class "Default")
      (node (ref "C20") (pin "2") (pinfunction "2_2") (pintype "passive"))
      (node (ref "IC1") (pin "18") (pinfunction "3FG_PA7_18") (pintype "input"))
      (node (ref "IC1") (pin "43") (pinfunction "OP2O_43") (pintype "input"))
      (node (ref "R34") (pin "2") (pinfunction "2_2") (pintype "passive"))
    )
    (net (code "45") (name "OP2P") (class "Default")
      (node (ref "IC1") (pin "41") (pinfunction "OP2P_41") (pintype "input"))
      (node (ref "R22") (pin "2") (pinfunction "2_2") (pintype "passive"))
      (node (ref "R29") (pin "2") (pinfunction "2_2") (pintype "passive"))
      (node (ref "R30") (pin "1") (pinfunction "1_1") (pintype "passive"))
    )
    (net (code "46") (name "OP3N") (class "Default")
      (node (ref "C21") (pin "1") (pinfunction "1_1") (pintype "passive"))
      (node (ref "IC1") (pin "46") (pinfunction "OP3N_46") (pintype "input"))
      (node (ref "R36") (pin "2") (pinfunction "2_2") (pintype "passive"))
      (node (ref "R37") (pin "1") (pinfunction "1_1") (pintype "passive"))
    )
    (net (code "47") (name "OP3O") (class "Default")
      (node (ref "C21") (pin "2") (pinfunction "2_2") (pintype "passive"))
      (node (ref "IC1") (pin "17") (pinfunction "PA6_17") (pintype "input"))
      (node (ref "IC1") (pin "47") (pinfunction "OP3O_47") (pintype "input"))
      (node (ref "R37") (pin "2") (pinfunction "2_2") (pintype "passive"))
    )
    (net (code "48") (name "OP3P") (class "Default")
      (node (ref "IC1") (pin "45") (pinfunction "OP3P_45") (pintype "input"))
      (node (ref "R23") (pin "2") (pinfunction "2_2") (pintype "passive"))
      (node (ref "R31") (pin "2") (pinfunction "2_2") (pintype "passive"))
      (node (ref "R32") (pin "1") (pinfunction "1_1") (pintype "passive"))
    )
    (net (code "49") (name "OUTU") (class "Default")
      (node (ref "C1") (pin "2") (pinfunction "2_2") (pintype "passive"))
      (node (ref "C18") (pin "1") (pinfunction "1_1") (pintype "passive"))
      (node (ref "IC1") (pin "34") (pinfunction "OUTU_34") (pintype "input"))
      (node (ref "Q1") (pin "3") (pinfunction "S_3") (pintype "passive"))
      (node (ref "Q2") (pin "2") (pinfunction "D_2") (pintype "passive"))
      (node (ref "U$2") (pin "1") (pinfunction "A_1") (pintype "bidirectional"))
    )
    (net (code "50") (name "OUTV") (class "Default")
      (node (ref "C17") (pin "1") (pinfunction "1_1") (pintype "passive"))
      (node (ref "C2") (pin "2") (pinfunction "2_2") (pintype "passive"))
      (node (ref "IC1") (pin "30") (pinfunction "OUTV_30") (pintype "input"))
      (node (ref "Q3") (pin "3") (pinfunction "S_3") (pintype "passive"))
      (node (ref "Q4") (pin "2") (pinfunction "D_2") (pintype "passive"))
      (node (ref "U$2") (pin "2") (pinfunction "B_2") (pintype "bidirectional"))
    )
    (net (code "51") (name "OUTW") (class "Default")
      (node (ref "C19") (pin "1") (pinfunction "1_1") (pintype "passive"))
      (node (ref "C22") (pin "2") (pinfunction "2_2") (pintype "passive"))
      (node (ref "IC1") (pin "26") (pinfunction "OUTW_26") (pintype "input"))
      (node (ref "Q5") (pin "3") (pinfunction "S_3") (pintype "passive"))
      (node (ref "Q6") (pin "2") (pinfunction "D_2") (pintype "passive"))
      (node (ref "U$2") (pin "3") (pinfunction "C_3") (pintype "bidirectional"))
    )
    (net (code "52") (name "PA3") (class "Default")
      (node (ref "IC1") (pin "14") (pinfunction "PA3_14") (pintype "input"))
      (node (ref "IO") (pin "9") (pinfunction "9_9") (pintype "passive"))
    )
    (net (code "53") (name "PA4") (class "Default")
      (node (ref "IC1") (pin "15") (pinfunction "PA4_15") (pintype "input"))
      (node (ref "IO") (pin "12") (pinfunction "12_12") (pintype "passive"))
    )
    (net (code "54") (name "PF0") (class "Default")
      (node (ref "IC1") (pin "4") (pinfunction "PF0_4") (pintype "input"))
      (node (ref "IO") (pin "5") (pinfunction "5_5") (pintype "passive"))
    )
    (net (code "55") (name "PF1") (class "Default")
      (node (ref "IC1") (pin "5") (pinfunction "PF1_5") (pintype "input"))
      (node (ref "IO") (pin "6") (pinfunction "6_6") (pintype "passive"))
    )
    (net (code "56") (name "SWDCLK") (class "Default")
      (node (ref "IC1") (pin "38") (pinfunction "PA14_SWD_CLK_38") (pintype "input"))
      (node (ref "PROG") (pin "4") (pinfunction "SWCLK_4") (pintype "bidirectional"))
    )
    (net (code "57") (name "SWDIO") (class "Default")
      (node (ref "IC1") (pin "37") (pinfunction "PA13_SWD_IO_37") (pintype "input"))
      (node (ref "PROG") (pin "2") (pinfunction "SWDIO_2") (pintype "bidirectional"))
    )
    (net (code "58") (name "UART_RX") (class "Default")
      (node (ref "IC1") (pin "40") (pinfunction "PB7_40") (pintype "input"))
      (node (ref "IO") (pin "3") (pinfunction "3_3") (pintype "passive"))
    )
    (net (code "59") (name "UART_TX") (class "Default")
      (node (ref "IC1") (pin "39") (pinfunction "PB6_39") (pintype "input"))
      (node (ref "IO") (pin "4") (pinfunction "4_4") (pintype "passive"))
    )
    (net (code "60") (name "V_BATT") (class "Default")
      (node (ref "C11") (pin "+") (pinfunction "+_+") (pintype "passive"))
      (node (ref "C16") (pin "+") (pinfunction "+_+") (pintype "passive"))
      (node (ref "C5") (pin "1") (pinfunction "1_1") (pintype "passive"))
      (node (ref "C8") (pin "+") (pinfunction "+_+") (pintype "passive"))
      (node (ref "C9") (pin "+") (pinfunction "+_+") (pintype "passive"))
      (node (ref "IC1") (pin "8") (pinfunction "VM_8") (pintype "input"))
      (node (ref "Q1") (pin "2") (pinfunction "D_2") (pintype "passive"))
      (node (ref "Q3") (pin "2") (pinfunction "D_2") (pintype "passive"))
      (node (ref "Q5") (pin "2") (pinfunction "D_2") (pintype "passive"))
      (node (ref "R1") (pin "2") (pinfunction "2_2") (pintype "passive"))
      (node (ref "U$3") (pin "+") (pinfunction "+_+") (pintype "bidirectional"))
    )
    (net (code "61") (name "unconnected-(IC1-OP4N-Pad2)") (class "Default")
      (node (ref "IC1") (pin "2") (pinfunction "OP4N_2") (pintype "input"))
    )
    (net (code "62") (name "unconnected-(IC1-OP4O-Pad3)") (class "Default")
      (node (ref "IC1") (pin "3") (pinfunction "OP4O_3") (pintype "input"))
    )
    (net (code "63") (name "unconnected-(IC1-OP4P-Pad1)") (class "Default")
      (node (ref "IC1") (pin "1") (pinfunction "OP4P_1") (pintype "input"))
    )
    (net (code "64") (name "unconnected-(PROG-SWO-Pad6)") (class "Default")
      (node (ref "PROG") (pin "6") (pinfunction "SWO_6") (pintype "bidirectional"))
    )
  )
)
